# 3S_4S.net
KiCad netlist of a schematic drawn in Altium Designer
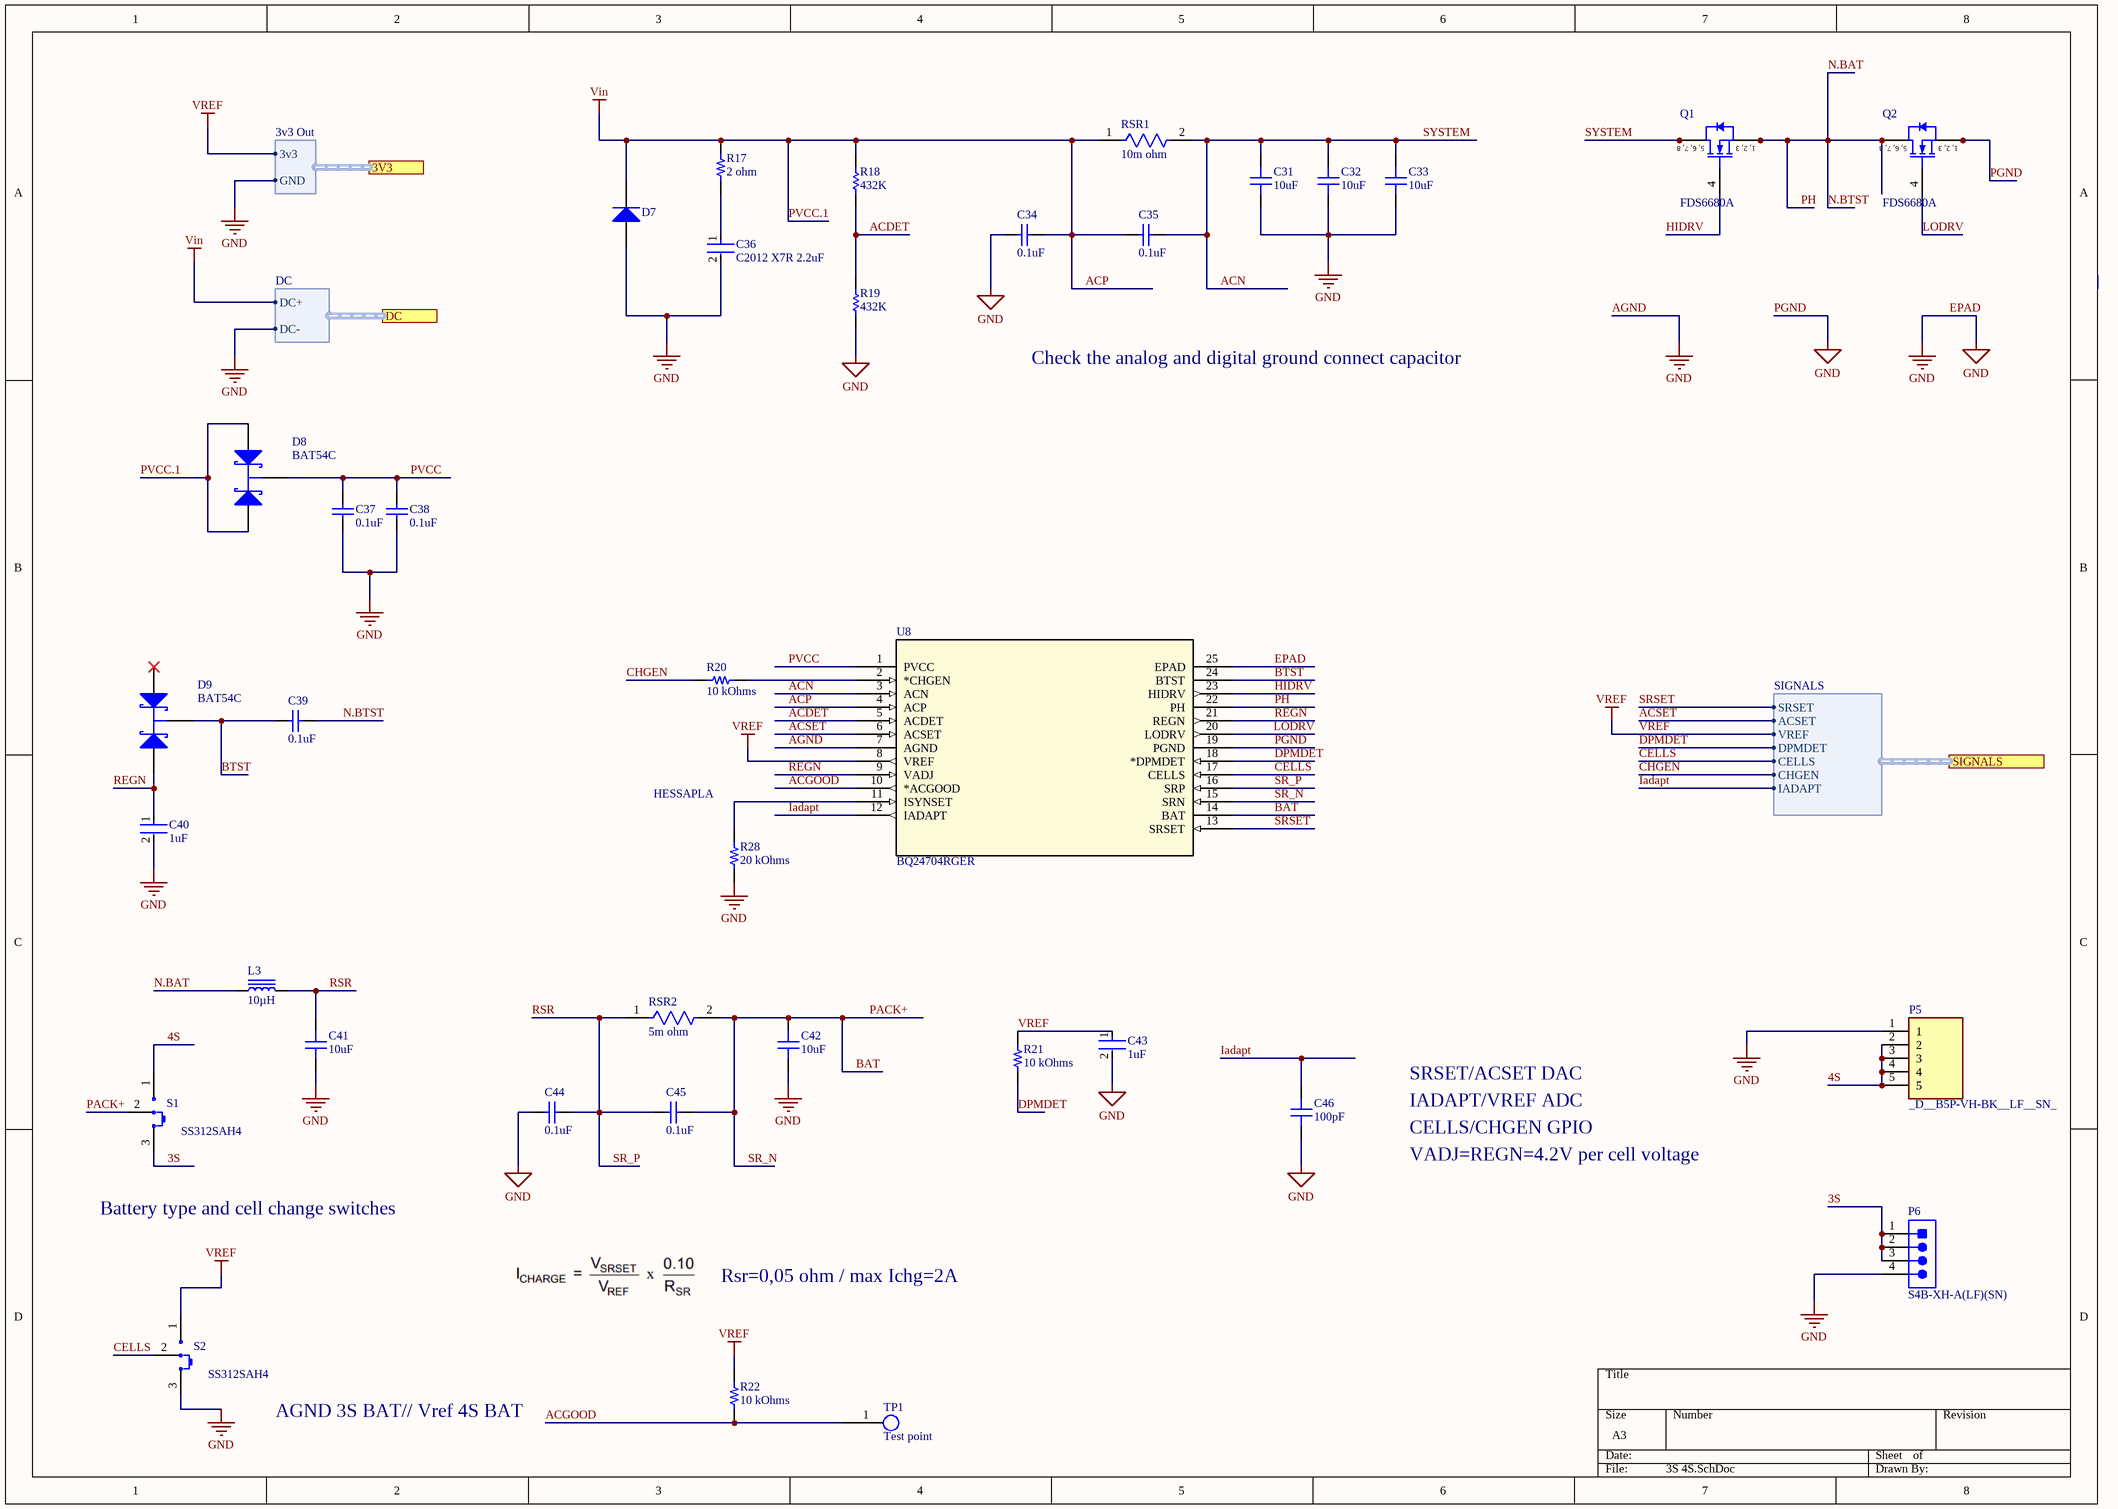
[diagram p0: 3S 4S.SchDoc]

(export (version "E")
  (design (tool "Eeschema 10.0.6"))
  (components
    (comp (ref "C31")
      (value "10uF")
      (footprint "CAP 1206_3216 - 0.8MM")
      (description "10µF, 25V, 20%, X5R, 1206")
      (fields (field (name "PART NUMBER") "CC1206JRNPO0BN272") (field (name "MANUFACTURER") "Yageo"))
      (libsource (lib "Celestial Altium Library - altium_library (2)") (part "Capacitor"))
    )
    (comp (ref "C32")
      (value "10uF")
      (footprint "CAP 1206_3216 - 0.8MM")
      (description "10µF, 25V, 20%, X5R, 1206")
      (fields (field (name "PART NUMBER") "CC1206JRNPO0BN272") (field (name "MANUFACTURER") "Yageo"))
      (libsource (lib "Celestial Altium Library - altium_library (2)") (part "Capacitor"))
    )
    (comp (ref "C33")
      (value "10uF")
      (footprint "CAP 1206_3216 - 0.8MM")
      (description "10µF, 25V, 20%, X5R, 1206")
      (fields (field (name "PART NUMBER") "CC1206JRNPO0BN272") (field (name "MANUFACTURER") "Yageo"))
      (libsource (lib "Celestial Altium Library - altium_library (2)") (part "Capacitor"))
    )
    (comp (ref "C34")
      (value "0.1uF")
      (footprint "CAPC2013X94X50NL20T25")
      (description "0.1µF, 50V, 10%, X7R, 0805")
      (fields
        (field (name "MANUFACTURER") "AVX Interconnect / Elco")
        (field (name "PART NUMBER") "08051C104JAT2A")
      )
      (libsource (lib "Altium Content Vault") (part "CAP"))
    )
    (comp (ref "C35")
      (value "0.1uF")
      (footprint "CAPC2013X94X50NL20T25")
      (description "0.1µF, 50V, 10%, X7R, 0805")
      (fields
        (field (name "MANUFACTURER") "AVX Interconnect / Elco")
        (field (name "PART NUMBER") "08051C104JAT2A")
      )
      (libsource (lib "Altium Content Vault") (part "CAP"))
    )
    (comp (ref "C36")
      (value "C2012 X7R 2.2uF")
      (footprint "FP-C2012-125-0_2-IPC_B")
      (description "Multilayer Ceramic Capacitors 2.2μF ±10% 50V X7R SMD 0805")
      (fields (field (name "VOLTAGE") "50V") (field (name "TOLERANCE") "10%"))
      (libsource (lib "Altium Content Vault") (part "b4654b650e69147ec39a6b967a45e02"))
    )
    (comp (ref "C37")
      (value "0.1uF")
      (footprint "CAPC2013X94X50NL20T25")
      (description "0.1µF, 50V, 10%, X7R, 0805")
      (fields
        (field (name "MANUFACTURER") "AVX Interconnect / Elco")
        (field (name "PART NUMBER") "08051C104JAT2A")
      )
      (libsource (lib "Altium Content Vault") (part "CAP"))
    )
    (comp (ref "C38")
      (value "0.1uF")
      (footprint "CAPC2013X94X50NL20T25")
      (description "0.1µF, 50V, 10%, X7R, 0805")
      (fields
        (field (name "MANUFACTURER") "AVX Interconnect / Elco")
        (field (name "PART NUMBER") "08051C104JAT2A")
      )
      (libsource (lib "Altium Content Vault") (part "CAP"))
    )
    (comp (ref "C39")
      (value "0.1uF")
      (footprint "CAPC2013X94X50NL20T25")
      (description "0.1µF, 50V, 10%, X7R, 0805")
      (fields
        (field (name "MANUFACTURER") "AVX Interconnect / Elco")
        (field (name "PART NUMBER") "08051C104JAT2A")
      )
      (libsource (lib "Altium Content Vault") (part "CAP"))
    )
    (comp (ref "C40")
      (value "1uF")
      (footprint "FP-C2012-125-0_2-IPC_B")
      (description "1µF, 25V, 10%, X7R, 2012, TDK")
      (fields (field (name "VOLTAGE") "100V") (field (name "TOLERANCE") "10%"))
      (libsource (lib "Altium Content Vault") (part "b4654b650e69147ec39a6b967a45e02"))
    )
    (comp (ref "C41")
      (value "10uF")
      (footprint "CAP 1206_3216 - 0.8MM")
      (description "10µF, 25V, 20%, X5R, 1206")
      (fields (field (name "PART NUMBER") "CC1206JRNPO0BN272") (field (name "MANUFACTURER") "Yageo"))
      (libsource (lib "Celestial Altium Library - altium_library (2)") (part "Capacitor"))
    )
    (comp (ref "C42")
      (value "10uF")
      (footprint "CAP 1206_3216 - 0.8MM")
      (description "10µF, 25V, 20%, X5R, 1206")
      (fields (field (name "PART NUMBER") "CC1206JRNPO0BN272") (field (name "MANUFACTURER") "Yageo"))
      (libsource (lib "Celestial Altium Library - altium_library (2)") (part "Capacitor"))
    )
    (comp (ref "C43")
      (value "1uF")
      (footprint "FP-C2012-125-0_2-IPC_B")
      (description "1µF, 25V, 10%, X7R, 2012, TDK")
      (fields (field (name "VOLTAGE") "100V") (field (name "TOLERANCE") "10%"))
      (libsource (lib "Altium Content Vault") (part "b4654b650e69147ec39a6b967a45e02"))
    )
    (comp (ref "C44")
      (value "0.1uF")
      (footprint "CAPC2013X94X50NL20T25")
      (description "0.1µF, 50V, 10%, X7R, 0805")
      (fields
        (field (name "MANUFACTURER") "AVX Interconnect / Elco")
        (field (name "PART NUMBER") "08051C104JAT2A")
      )
      (libsource (lib "Altium Content Vault") (part "CAP"))
    )
    (comp (ref "C45")
      (value "0.1uF")
      (footprint "CAPC2013X94X50NL20T25")
      (description "0.1µF, 50V, 10%, X7R, 0805")
      (fields
        (field (name "MANUFACTURER") "AVX Interconnect / Elco")
        (field (name "PART NUMBER") "08051C104JAT2A")
      )
      (libsource (lib "Altium Content Vault") (part "CAP"))
    )
    (comp (ref "C46")
      (value "100pF")
      (footprint "CAP 1206_3216 - 0.8MM")
      (description "100pF, 25V, 10%, X7R, 0805,")
      (fields (field (name "PART NUMBER") "CC1206JRNPO0BN272") (field (name "MANUFACTURER") "Yageo"))
      (libsource (lib "Celestial Altium Library - altium_library (2)") (part "Capacitor"))
    )
    (comp (ref "D7")
      (value "~")
      (footprint "DIOD-SMA-2_A_V")
      (description "Ultra-Fast Rectifier, 1 A, 1.7 V, -65 to 150 degC, 2-Pin SMA, RoHS, Tape and Reel")
      (fields (field (name "MANUFACTURER") "Diodes Inc"))
      (libsource (lib "Altium Content Vault") (part "D-AK-2"))
    )
    (comp (ref "D8")
      (value "BAT54C")
      (footprint "NXP-SOT23-3_V")
      (description "Schottky Barrier Diode, 30 V, 2 uA, -55 to 150 degC, 3-Pin SOT23, RoHS, Tape and Reel")
      (fields (field (name "MANUFACTURER") "NXP Semiconductors"))
      (libsource (lib "Altium Content Vault") (part "NXP-DSKY_A1A2K3-3"))
    )
    (comp (ref "D9")
      (value "BAT54C")
      (footprint "NXP-SOT23-3_V")
      (description "Schottky Barrier Diode, 30 V, 2 uA, -55 to 150 degC, 3-Pin SOT23, RoHS, Tape and Reel")
      (fields (field (name "MANUFACTURER") "NXP Semiconductors"))
      (libsource (lib "Altium Content Vault") (part "NXP-DSKY_A1A2K3-3"))
    )
    (comp (ref "L3")
      (value "10µH")
      (footprint "BOURNS SRP5030T")
      (description "FIXED IND 10UH 2.75A 128MOHM SMD")
      (fields (field (name "PART NUMBER") "SRP5030T-100M") (field (name "MANUFACTURER") "Bourns Inc."))
      (libsource (lib "Celestial Altium Library - altium_library (2)") (part "Inductor"))
    )
    (comp (ref "P5")
      (value "_D__B5P-VH-BK__LF__SN_")
      (footprint "SamacSys:SHDR5W114P0X396_1X5_1974X850X1090P")
      (description "Connector")
      (fields (field (name "MANUFACTURER_PART_NUMBER") "(D) B5P-VH-BK (LF)(SN)"))
      (libsource (lib "*") (part "_D__B5P-VH-BK__LF__SN_"))
    )
    (comp (ref "P6")
      (value "S4B-XH-A(LF)(SN)")
      (footprint "JST-S4B-XH-A(LF)(SN)_V")
      (libsource (lib "Altium Content Vault") (part "CN-1P-M-R4"))
    )
    (comp (ref "Q1")
      (value "FDS6680A")
      (footprint "FAIR-SOIC-8_V")
      (fields (field (name "MANUFACTURER") "Fairchild Semiconductor"))
      (libsource (lib "Altium Content Vault") (part "NEMOS-SSSGDDDD-8"))
    )
    (comp (ref "Q2")
      (value "FDS6680A")
      (footprint "FAIR-SOIC-8_V")
      (fields (field (name "MANUFACTURER") "Fairchild Semiconductor"))
      (libsource (lib "Altium Content Vault") (part "NEMOS-SSSGDDDD-8"))
    )
    (comp (ref "R17")
      (value "2 ohm")
      (footprint "RES 1210_3225")
      (description "RES 3.3K OHM 5% 1/2W 1210")
      (fields
        (field (name "PART NUMBER") "RK73B2ETTD332J")
        (field (name "MANUFACTURER") "KOA Speer Electronics, Inc.")
      )
      (libsource (lib "Celestial Altium Library - altium_library (2)") (part "Resistor"))
    )
    (comp (ref "R18")
      (value "432K")
      (footprint "RESC1005X40X25NL05T10")
      (description "432K,1/16W, %1")
      (fields (field (name "MANUFACTURER") "Yageo / Phycomp") (field (name "PART NUMBER") "RC0402JR-070RL"))
      (libsource (lib "Altium Content Vault") (part "RES"))
    )
    (comp (ref "R19")
      (value "432K")
      (footprint "RESC1005X40X25NL05T10")
      (description "432K,1/16W, %1")
      (fields (field (name "MANUFACTURER") "Yageo / Phycomp") (field (name "PART NUMBER") "RC0402JR-070RL"))
      (libsource (lib "Altium Content Vault") (part "RES"))
    )
    (comp (ref "R20")
      (value "10 kOhms")
      (footprint "RES 0603_1608")
      (description "RES 10K OHM 0.1% 1/16W 0603")
      (fields
        (field (name "PART NUMBER") "RNCS0603BKE10K0")
        (field (name "MANUFACTURER") "Stackpole Electronics Inc")
      )
      (libsource (lib "Celestial Altium Library - altium_library (2)") (part "Resistor"))
    )
    (comp (ref "R21")
      (value "10 kOhms")
      (footprint "RES 0603_1608")
      (description "RES 10K OHM 0.1% 1/16W 0603")
      (fields
        (field (name "PART NUMBER") "RNCS0603BKE10K0")
        (field (name "MANUFACTURER") "Stackpole Electronics Inc")
      )
      (libsource (lib "Celestial Altium Library - altium_library (2)") (part "Resistor"))
    )
    (comp (ref "R22")
      (value "10 kOhms")
      (footprint "RES 0603_1608")
      (description "RES 10K OHM 0.1% 1/16W 0603")
      (fields
        (field (name "PART NUMBER") "RNCS0603BKE10K0")
        (field (name "MANUFACTURER") "Stackpole Electronics Inc")
      )
      (libsource (lib "Celestial Altium Library - altium_library (2)") (part "Resistor"))
    )
    (comp (ref "R28")
      (value "20 kOhms")
      (footprint "RES 0603_1608")
      (description "RES 10K OHM 0.1% 1/16W 0603")
      (fields
        (field (name "PART NUMBER") "RNCS0603BKE10K0")
        (field (name "MANUFACTURER") "Stackpole Electronics Inc")
      )
      (libsource (lib "Celestial Altium Library - altium_library (2)") (part "Resistor"))
    )
    (comp (ref "RSR1")
      (value "10m ohm")
      (footprint "FP-CSRN2010-IPC_A")
      (description "RES 0.01 OHM 1% 1W 2010")
      (fields (field (name "TOLERANCE") "1%"))
      (libsource (lib "Altium Content Vault") (part "1029c3af85768c4190bb7ad29bc67b5"))
    )
    (comp (ref "RSR2")
      (value "5m ohm")
      (footprint "FP-CSRN2010-IPC_A")
      (fields (field (name "TOLERANCE") "1%"))
      (libsource (lib "Altium Content Vault") (part "1029c3af85768c4190bb7ad29bc67b5"))
    )
    (comp (ref "S1")
      (value "SS312SAH4")
      (footprint "NKK SS312SAH4")
      (description "SWITCH SLIDE SPDT 0.4VA 28V")
      (fields (field (name "MANUFACTURER") "NKK Switches"))
      (libsource (lib "Celestial Altium Library - altium_library (2)") (part "NKK SS312"))
    )
    (comp (ref "S2")
      (value "SS312SAH4")
      (footprint "NKK SS312SAH4")
      (description "SWITCH SLIDE SPDT 0.4VA 28V")
      (fields (field (name "MANUFACTURER") "NKK Switches"))
      (libsource (lib "Celestial Altium Library - altium_library (2)") (part "NKK SS312"))
    )
    (comp (ref "TP1")
      (value "Test point")
      (footprint "Test Point")
      (libsource (lib "Schlib1") (part "Test point"))
    )
    (comp (ref "U8")
      (value "BQ24704RGER")
      (footprint "RGE24_2P45X2P45")
      (description "Unknown")
      (fields
        (field (name "MANUFACTURER") "Texas Instruments")
        (field (name "GENERIC_PART_NUMBER") "BQ24704")
        (field (name "COPYRIGHT") "Copyright (C) 2021 Accelerated Designs. All rights reserved")
      )
      (libsource (lib "Schlib1") (part "BQ24704RGER"))
    )
  )
  (nets
    (net (code "5") (name "/3S") (class "Default")
      (node (ref "P6") (pin "1") (pinfunction "1_1") (pintype "passive"))
      (node (ref "P6") (pin "2") (pinfunction "2_2") (pintype "passive"))
      (node (ref "P6") (pin "3") (pinfunction "3_3") (pintype "passive"))
      (node (ref "S1") (pin "3") (pinfunction "3_3") (pintype "passive"))
    )
    (net (code "6") (name "/4S") (class "Default")
      (node (ref "P5") (pin "2") (pinfunction "2_2") (pintype "passive"))
      (node (ref "P5") (pin "3") (pinfunction "3_3") (pintype "passive"))
      (node (ref "P5") (pin "4") (pinfunction "4_4") (pintype "passive"))
      (node (ref "P5") (pin "5") (pinfunction "5_5") (pintype "passive"))
      (node (ref "S1") (pin "1") (pinfunction "1_1") (pintype "passive"))
    )
    (net (code "7") (name "/ACDET") (class "Default")
      (node (ref "R18") (pin "1") (pinfunction "1_1") (pintype "passive"))
      (node (ref "R19") (pin "2") (pinfunction "2_2") (pintype "passive"))
      (node (ref "U8") (pin "5") (pinfunction "ACDET_5") (pintype "input"))
    )
    (net (code "8") (name "/ACGOOD") (class "Default")
      (node (ref "R22") (pin "1") (pinfunction "1_1") (pintype "passive"))
      (node (ref "TP1") (pin "1") (pinfunction "0_1") (pintype "passive"))
      (node (ref "U8") (pin "10") (pinfunction "*ACGOOD_10") (pintype "output"))
    )
    (net (code "9") (name "/ACN") (class "Default")
      (node (ref "C31") (pin "2") (pinfunction "2_2") (pintype "passive"))
      (node (ref "C32") (pin "2") (pinfunction "2_2") (pintype "passive"))
      (node (ref "C33") (pin "2") (pinfunction "2_2") (pintype "passive"))
      (node (ref "C35") (pin "2") (pinfunction "2_2") (pintype "passive"))
      (node (ref "Q1") (pin "5") (pinfunction "D_5") (pintype "passive"))
      (node (ref "Q1") (pin "6") (pinfunction "D_6") (pintype "passive"))
      (node (ref "Q1") (pin "7") (pinfunction "D_7") (pintype "passive"))
      (node (ref "Q1") (pin "8") (pinfunction "D_8") (pintype "passive"))
      (node (ref "RSR1") (pin "2") (pinfunction "2_2") (pintype "passive"))
      (node (ref "U8") (pin "3") (pinfunction "ACN_3") (pintype "input"))
    )
    (net (code "10") (name "/ACSET") (class "Default")
      (node (ref "U8") (pin "6") (pinfunction "ACSET_6") (pintype "input"))
    )
    (net (code "11") (name "/BAT") (class "Default")
      (node (ref "C42") (pin "2") (pinfunction "2_2") (pintype "passive"))
      (node (ref "C45") (pin "2") (pinfunction "2_2") (pintype "passive"))
      (node (ref "RSR2") (pin "2") (pinfunction "2_2") (pintype "passive"))
      (node (ref "S1") (pin "2") (pinfunction "COM_2") (pintype "passive"))
      (node (ref "U8") (pin "14") (pinfunction "BAT_14") (pintype "passive"))
      (node (ref "U8") (pin "15") (pinfunction "SRN_15") (pintype "input"))
    )
    (net (code "12") (name "/BTST") (class "Default")
      (node (ref "C39") (pin "1") (pinfunction "1_1") (pintype "passive"))
      (node (ref "D9") (pin "3") (pinfunction "K_3") (pintype "passive"))
      (node (ref "U8") (pin "24") (pinfunction "BTST_24") (pintype "passive"))
    )
    (net (code "13") (name "/CELLS") (class "Default")
      (node (ref "S2") (pin "2") (pinfunction "COM_2") (pintype "passive"))
      (node (ref "U8") (pin "17") (pinfunction "CELLS_17") (pintype "input"))
    )
    (net (code "14") (name "/CHGEN") (class "Default")
      (node (ref "R20") (pin "2") (pinfunction "2_2") (pintype "passive"))
    )
    (net (code "15") (name "/DPMDET") (class "Default")
      (node (ref "R21") (pin "1") (pinfunction "1_1") (pintype "passive"))
      (node (ref "U8") (pin "18") (pinfunction "*DPMDET_18") (pintype "input"))
    )
    (net (code "16") (name "/HIDRV") (class "Default")
      (node (ref "Q1") (pin "4") (pinfunction "G_4") (pintype "passive"))
      (node (ref "U8") (pin "23") (pinfunction "HIDRV_23") (pintype "output"))
    )
    (net (code "17") (name "/Iadapt") (class "Default")
      (node (ref "C46") (pin "2") (pinfunction "2_2") (pintype "passive"))
      (node (ref "U8") (pin "12") (pinfunction "IADAPT_12") (pintype "output"))
    )
    (net (code "18") (name "/LODRV") (class "Default")
      (node (ref "Q2") (pin "4") (pinfunction "G_4") (pintype "passive"))
      (node (ref "U8") (pin "20") (pinfunction "LODRV_20") (pintype "output"))
    )
    (net (code "19") (name "/N.BAT") (class "Default")
      (node (ref "C39") (pin "2") (pinfunction "2_2") (pintype "passive"))
      (node (ref "L3") (pin "1") (pinfunction "1_1") (pintype "passive"))
      (node (ref "Q1") (pin "1") (pinfunction "S_1") (pintype "passive"))
      (node (ref "Q1") (pin "2") (pinfunction "S_2") (pintype "passive"))
      (node (ref "Q1") (pin "3") (pinfunction "S_3") (pintype "passive"))
      (node (ref "Q2") (pin "5") (pinfunction "D_5") (pintype "passive"))
      (node (ref "Q2") (pin "6") (pinfunction "D_6") (pintype "passive"))
      (node (ref "Q2") (pin "7") (pinfunction "D_7") (pintype "passive"))
      (node (ref "Q2") (pin "8") (pinfunction "D_8") (pintype "passive"))
      (node (ref "U8") (pin "22") (pinfunction "PH_22") (pintype "passive"))
    )
    (net (code "20") (name "/PVCC") (class "Default")
      (node (ref "C37") (pin "2") (pinfunction "2_2") (pintype "passive"))
      (node (ref "C38") (pin "2") (pinfunction "2_2") (pintype "passive"))
      (node (ref "D8") (pin "3") (pinfunction "K_3") (pintype "passive"))
      (node (ref "U8") (pin "1") (pinfunction "PVCC_1") (pintype "power_in"))
    )
    (net (code "21") (name "/REGN") (class "Default")
      (node (ref "C40") (pin "1") (pinfunction "1_1") (pintype "passive"))
      (node (ref "D9") (pin "2") (pinfunction "A_2") (pintype "passive"))
      (node (ref "U8") (pin "21") (pinfunction "REGN_21") (pintype "output"))
      (node (ref "U8") (pin "9") (pinfunction "VADJ_9") (pintype "input"))
    )
    (net (code "22") (name "/RSR") (class "Default")
      (node (ref "C41") (pin "2") (pinfunction "2_2") (pintype "passive"))
      (node (ref "C44") (pin "2") (pinfunction "2_2") (pintype "passive"))
      (node (ref "C45") (pin "1") (pinfunction "1_1") (pintype "passive"))
      (node (ref "L3") (pin "2") (pinfunction "2_2") (pintype "passive"))
      (node (ref "RSR2") (pin "1") (pinfunction "1_1") (pintype "passive"))
      (node (ref "U8") (pin "16") (pinfunction "SRP_16") (pintype "input"))
    )
    (net (code "23") (name "/SRSET") (class "Default")
      (node (ref "U8") (pin "13") (pinfunction "SRSET_13") (pintype "input"))
    )
    (net (code "27") (name "GND") (class "Default")
      (node (ref "C31") (pin "1") (pinfunction "1_1") (pintype "passive"))
      (node (ref "C32") (pin "1") (pinfunction "1_1") (pintype "passive"))
      (node (ref "C33") (pin "1") (pinfunction "1_1") (pintype "passive"))
      (node (ref "C34") (pin "1") (pinfunction "1_1") (pintype "passive"))
      (node (ref "C36") (pin "2") (pinfunction "2_2") (pintype "passive"))
      (node (ref "C37") (pin "1") (pinfunction "1_1") (pintype "passive"))
      (node (ref "C38") (pin "1") (pinfunction "1_1") (pintype "passive"))
      (node (ref "C40") (pin "2") (pinfunction "2_2") (pintype "passive"))
      (node (ref "C41") (pin "1") (pinfunction "1_1") (pintype "passive"))
      (node (ref "C42") (pin "1") (pinfunction "1_1") (pintype "passive"))
      (node (ref "C43") (pin "2") (pinfunction "2_2") (pintype "passive"))
      (node (ref "C44") (pin "1") (pinfunction "1_1") (pintype "passive"))
      (node (ref "C46") (pin "1") (pinfunction "1_1") (pintype "passive"))
      (node (ref "D7") (pin "1") (pinfunction "A_1") (pintype "passive"))
      (node (ref "P5") (pin "1") (pinfunction "1_1") (pintype "passive"))
      (node (ref "P6") (pin "4") (pinfunction "4_4") (pintype "passive"))
      (node (ref "Q2") (pin "1") (pinfunction "S_1") (pintype "passive"))
      (node (ref "Q2") (pin "2") (pinfunction "S_2") (pintype "passive"))
      (node (ref "Q2") (pin "3") (pinfunction "S_3") (pintype "passive"))
      (node (ref "R19") (pin "1") (pinfunction "1_1") (pintype "passive"))
      (node (ref "R28") (pin "1") (pinfunction "1_1") (pintype "passive"))
      (node (ref "S2") (pin "3") (pinfunction "3_3") (pintype "passive"))
      (node (ref "U8") (pin "19") (pinfunction "PGND_19") (pintype "power_in"))
      (node (ref "U8") (pin "25") (pinfunction "EPAD_25") (pintype "power_in"))
      (node (ref "U8") (pin "7") (pinfunction "AGND_7") (pintype "power_in"))
    )
    (net (code "28") (name "Net-(C36-Pad1)") (class "Default")
      (node (ref "C36") (pin "1") (pinfunction "1_1") (pintype "passive"))
      (node (ref "R17") (pin "1") (pinfunction "1_1") (pintype "passive"))
    )
    (net (code "29") (name "Net-(U8-*CHGEN)") (class "Default")
      (node (ref "R20") (pin "1") (pinfunction "1_1") (pintype "passive"))
      (node (ref "U8") (pin "2") (pinfunction "*CHGEN_2") (pintype "input"))
    )
    (net (code "30") (name "Net-(U8-ISYNSET)") (class "Default")
      (node (ref "R28") (pin "2") (pinfunction "2_2") (pintype "passive"))
      (node (ref "U8") (pin "11") (pinfunction "ISYNSET_11") (pintype "input"))
    )
    (net (code "31") (name "VREF") (class "Default")
      (node (ref "C43") (pin "1") (pinfunction "1_1") (pintype "passive"))
      (node (ref "R21") (pin "2") (pinfunction "2_2") (pintype "passive"))
      (node (ref "R22") (pin "2") (pinfunction "2_2") (pintype "passive"))
      (node (ref "S2") (pin "1") (pinfunction "1_1") (pintype "passive"))
      (node (ref "U8") (pin "8") (pinfunction "VREF_8") (pintype "output"))
    )
    (net (code "32") (name "Vin") (class "Default")
      (node (ref "C34") (pin "2") (pinfunction "2_2") (pintype "passive"))
      (node (ref "C35") (pin "1") (pinfunction "1_1") (pintype "passive"))
      (node (ref "D7") (pin "2") (pinfunction "K_2") (pintype "passive"))
      (node (ref "D8") (pin "1") (pinfunction "A_1") (pintype "passive"))
      (node (ref "D8") (pin "2") (pinfunction "A_2") (pintype "passive"))
      (node (ref "R17") (pin "2") (pinfunction "2_2") (pintype "passive"))
      (node (ref "R18") (pin "2") (pinfunction "2_2") (pintype "passive"))
      (node (ref "RSR1") (pin "1") (pinfunction "1_1") (pintype "passive"))
      (node (ref "U8") (pin "4") (pinfunction "ACP_4") (pintype "input"))
    )
    (net (code "33") (name "unconnected-(D9-A-Pad1)") (class "Default")
      (node (ref "D9") (pin "1") (pinfunction "A_1") (pintype "passive+no_connect"))
    )
  )
)
